# op-synth_2018-05-09.net
KiCad netlist of a schematic drawn in EAGLE
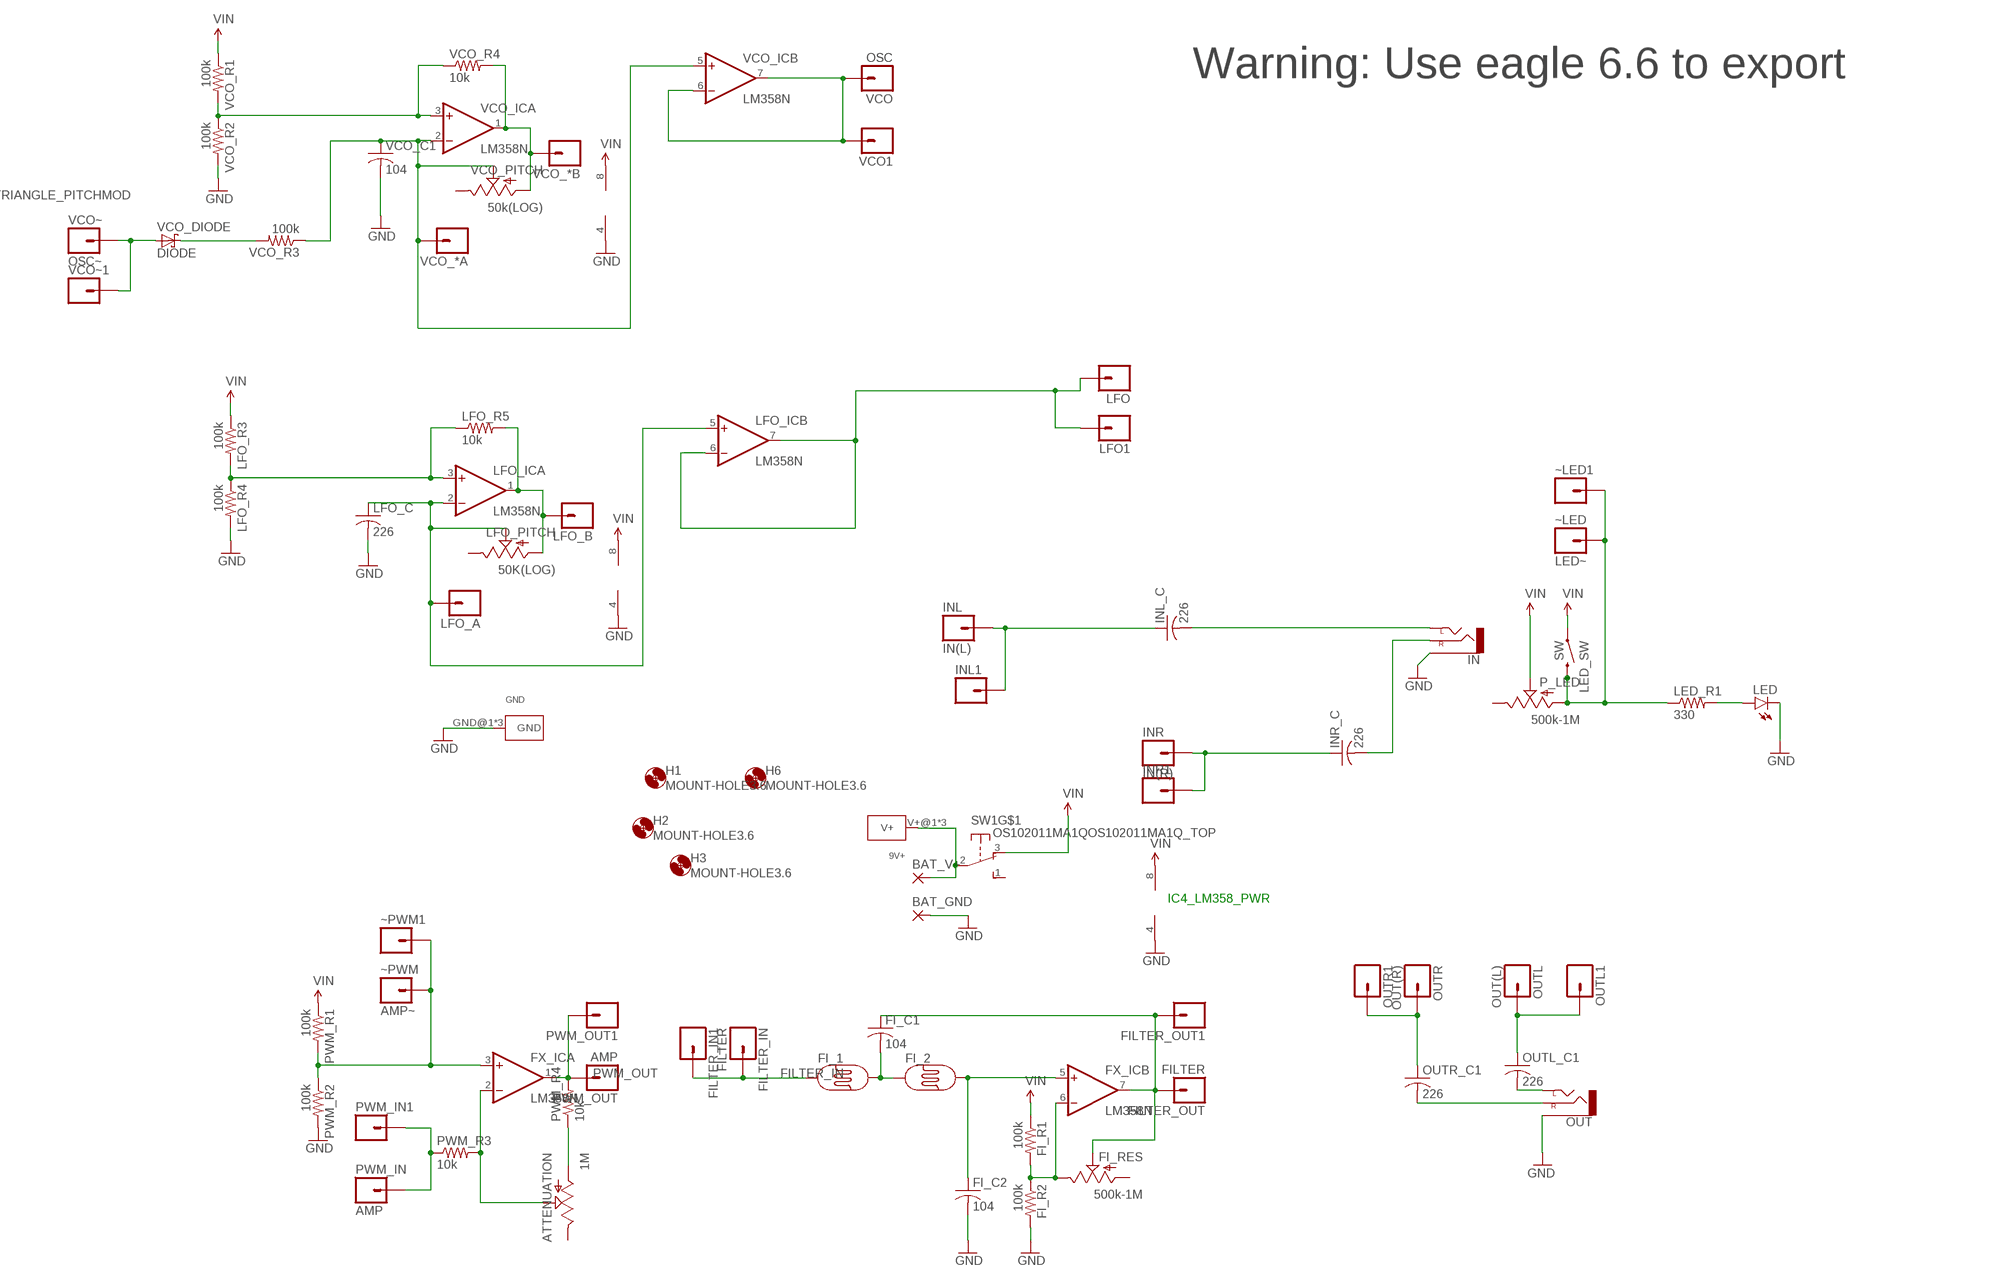
[diagram p0: schematic, sheet 1]

(export (version "E")
  (design (tool "Eeschema 10.0.6"))
  (components
    (comp (ref "9V+")
      (value "KEYSTONE-629+")
      (footprint "eagle-import:KEYSTONE_BATTAERY_TERMINAL-629+")
      (libsource (lib "eagle-import") (part "KEYSTONE-629+"))
    )
    (comp (ref "ATTENUATION")
      (value "1M")
      (footprint "eagle-import:TRIM_POT")
      (libsource (lib "eagle-import") (part "POTTRIM"))
    )
    (comp (ref "BAT_GND")
      (value "3,81/1,4")
      (footprint "eagle-import:3,81_1,4")
      (libsource (lib "eagle-import") (part "3,81/1,4"))
    )
    (comp (ref "BAT_V+")
      (value "3,81/1,4")
      (footprint "eagle-import:3,81_1,4")
      (libsource (lib "eagle-import") (part "3,81/1,4"))
    )
    (comp (ref "FILTER_IN")
      (value "FILTER")
      (footprint "eagle-import:1X01_SIDE_NAME")
      (libsource (lib "eagle-import") (part "HEADER-1X1"))
    )
    (comp (ref "FILTER_IN1")
      (value "HEADER-1X1")
      (footprint "eagle-import:1X01_SIDE_NAME")
      (libsource (lib "eagle-import") (part "HEADER-1X1"))
    )
    (comp (ref "FILTER_OUT")
      (value "FILTER")
      (footprint "eagle-import:1X01_SIDE_NAME")
      (libsource (lib "eagle-import") (part "HEADER-1X1"))
    )
    (comp (ref "FILTER_OUT1")
      (value "HEADER-1X1")
      (footprint "eagle-import:1X01_SIDE_NAME")
      (libsource (lib "eagle-import") (part "HEADER-1X1"))
    )
    (comp (ref "FI_1")
      (value "PHOTOCELLPTH")
      (footprint "eagle-import:PHOTOCELL")
      (libsource (lib "eagle-import") (part "PHOTOCELLPTH"))
    )
    (comp (ref "FI_2")
      (value "PHOTOCELLPTH")
      (footprint "eagle-import:PHOTOCELL")
      (libsource (lib "eagle-import") (part "PHOTOCELLPTH"))
    )
    (comp (ref "FI_C1")
      (value "104")
      (footprint "eagle-import:C050-024X044")
      (libsource (lib "eagle-import") (part "resistor_C-US050-024X044"))
    )
    (comp (ref "FI_C2")
      (value "104")
      (footprint "eagle-import:C050-024X044")
      (libsource (lib "eagle-import") (part "resistor_C-US050-024X044"))
    )
    (comp (ref "FI_R1")
      (value "100k")
      (footprint "eagle-import:0204_7")
      (libsource (lib "eagle-import") (part "R-US_0204/7"))
    )
    (comp (ref "FI_R2")
      (value "100k")
      (footprint "eagle-import:0204_7")
      (libsource (lib "eagle-import") (part "R-US_0204/7"))
    )
    (comp (ref "FI_RES")
      (value "500k-1M")
      (footprint "eagle-import:ALPS_POT")
      (libsource (lib "eagle-import") (part "POT"))
    )
    (comp (ref "FX_IC")
      (value "LM358N")
      (footprint "eagle-import:DIL08")
      (libsource (lib "eagle-import") (part "LM358N"))
    )
    (comp (ref "GND")
      (value "KEYSTONE-629")
      (footprint "eagle-import:KEYSTONE_AA_AAA_BATTERY_TERMINAL-629")
      (libsource (lib "eagle-import") (part "KEYSTONE-629"))
    )
    (comp (ref "H1")
      (value "MOUNT-HOLE3.6")
      (footprint "eagle-import:3,6")
      (libsource (lib "eagle-import") (part "MOUNT-HOLE3.6"))
    )
    (comp (ref "H2")
      (value "MOUNT-HOLE3.6")
      (footprint "eagle-import:3,6")
      (libsource (lib "eagle-import") (part "MOUNT-HOLE3.6"))
    )
    (comp (ref "H3")
      (value "MOUNT-HOLE3.6")
      (footprint "eagle-import:3,6")
      (libsource (lib "eagle-import") (part "MOUNT-HOLE3.6"))
    )
    (comp (ref "H6")
      (value "MOUNT-HOLE3.6")
      (footprint "eagle-import:3,6")
      (libsource (lib "eagle-import") (part "MOUNT-HOLE3.6"))
    )
    (comp (ref "IN")
      (value "AUDIO-JACKPTH")
      (footprint "eagle-import:AUDIO-JACK")
      (libsource (lib "eagle-import") (part "AUDIO-JACKPTH"))
    )
    (comp (ref "INL")
      (value "IN(L)")
      (footprint "eagle-import:1X01_SIDE_NAME")
      (libsource (lib "eagle-import") (part "HEADER-1X1"))
    )
    (comp (ref "INL1")
      (value "HEADER-1X1")
      (footprint "eagle-import:1X01_SIDE_NAME")
      (libsource (lib "eagle-import") (part "HEADER-1X1"))
    )
    (comp (ref "INL_C")
      (value "226")
      (footprint "eagle-import:C050-024X044")
      (libsource (lib "eagle-import") (part "C-US050-024X044"))
    )
    (comp (ref "INR")
      (value "IN(R)")
      (footprint "eagle-import:1X01_SIDE_NAME")
      (libsource (lib "eagle-import") (part "HEADER-1X1"))
    )
    (comp (ref "INR1")
      (value "HEADER-1X1")
      (footprint "eagle-import:1X01_SIDE_NAME")
      (libsource (lib "eagle-import") (part "HEADER-1X1"))
    )
    (comp (ref "INR_C")
      (value "226")
      (footprint "eagle-import:C050-024X044")
      (libsource (lib "eagle-import") (part "C-US050-024X044"))
    )
    (comp (ref "LED")
      (value "LED5MM")
      (footprint "eagle-import:LED5MM")
      (libsource (lib "eagle-import") (part "LED5MM"))
    )
    (comp (ref "LED_R1")
      (value "330")
      (footprint "eagle-import:0204_7")
      (libsource (lib "eagle-import") (part "R-US_0204/7"))
    )
    (comp (ref "LED_SW")
      (value "SW")
      (footprint "eagle-import:TACTILE-PTH-12MM")
      (libsource (lib "eagle-import") (part "SWITCH-MOMENTARY-212MM"))
    )
    (comp (ref "LFO")
      (value "HEADER-1X1")
      (footprint "eagle-import:1X01_SIDE_NAME")
      (libsource (lib "eagle-import") (part "HEADER-1X1"))
    )
    (comp (ref "LFO1")
      (value "HEADER-1X1")
      (footprint "eagle-import:1X01_SIDE_NAME")
      (libsource (lib "eagle-import") (part "HEADER-1X1"))
    )
    (comp (ref "LFO_A")
      (value "HEADER-1X1")
      (footprint "eagle-import:1X01_SIDE_NAME")
      (libsource (lib "eagle-import") (part "HEADER-1X1"))
    )
    (comp (ref "LFO_B")
      (value "HEADER-1X1")
      (footprint "eagle-import:1X01_SIDE_NAME")
      (libsource (lib "eagle-import") (part "HEADER-1X1"))
    )
    (comp (ref "LFO_C")
      (value "226")
      (footprint "eagle-import:C050-024X044")
      (libsource (lib "eagle-import") (part "resistor_C-US050-024X044"))
    )
    (comp (ref "LFO_IC")
      (value "LM358N")
      (footprint "eagle-import:DIL08")
      (libsource (lib "eagle-import") (part "LM358N"))
    )
    (comp (ref "LFO_PITCH")
      (value "50K(LOG)")
      (footprint "eagle-import:ALPS_POT")
      (libsource (lib "eagle-import") (part "POT"))
    )
    (comp (ref "LFO_R3")
      (value "100k")
      (footprint "eagle-import:0204_7")
      (libsource (lib "eagle-import") (part "R-US_0204/7"))
    )
    (comp (ref "LFO_R4")
      (value "100k")
      (footprint "eagle-import:0204_7")
      (libsource (lib "eagle-import") (part "R-US_0204/7"))
    )
    (comp (ref "LFO_R5")
      (value "10k")
      (footprint "eagle-import:0204_7")
      (libsource (lib "eagle-import") (part "R-US_0204/7"))
    )
    (comp (ref "OUT")
      (value "AUDIO-JACKPTH")
      (footprint "eagle-import:AUDIO-JACK")
      (libsource (lib "eagle-import") (part "AUDIO-JACKPTH"))
    )
    (comp (ref "OUTL")
      (value "OUT(L)")
      (footprint "eagle-import:1X01_SIDE_NAME")
      (libsource (lib "eagle-import") (part "HEADER-1X1"))
    )
    (comp (ref "OUTL1")
      (value "HEADER-1X1")
      (footprint "eagle-import:1X01_SIDE_NAME")
      (libsource (lib "eagle-import") (part "HEADER-1X1"))
    )
    (comp (ref "OUTL_C1")
      (value "226")
      (footprint "eagle-import:C050-024X044")
      (libsource (lib "eagle-import") (part "C-US050-024X044"))
    )
    (comp (ref "OUTR")
      (value "OUT(R)")
      (footprint "eagle-import:1X01_SIDE_NAME")
      (libsource (lib "eagle-import") (part "HEADER-1X1"))
    )
    (comp (ref "OUTR1")
      (value "HEADER-1X1")
      (footprint "eagle-import:1X01_SIDE_NAME")
      (libsource (lib "eagle-import") (part "HEADER-1X1"))
    )
    (comp (ref "OUTR_C1")
      (value "226")
      (footprint "eagle-import:C050-024X044")
      (libsource (lib "eagle-import") (part "C-US050-024X044"))
    )
    (comp (ref "PWM_IN")
      (value "AMP")
      (footprint "eagle-import:1X01_SIDE_NAME")
      (libsource (lib "eagle-import") (part "HEADER-1X1"))
    )
    (comp (ref "PWM_IN1")
      (value "HEADER-1X1")
      (footprint "eagle-import:1X01_SIDE_NAME")
      (libsource (lib "eagle-import") (part "HEADER-1X1"))
    )
    (comp (ref "PWM_OUT")
      (value "AMP")
      (footprint "eagle-import:1X01_SIDE_NAME")
      (libsource (lib "eagle-import") (part "HEADER-1X1"))
    )
    (comp (ref "PWM_OUT1")
      (value "HEADER-1X1")
      (footprint "eagle-import:1X01_SIDE_NAME")
      (libsource (lib "eagle-import") (part "HEADER-1X1"))
    )
    (comp (ref "PWM_R1")
      (value "100k")
      (footprint "eagle-import:0204_7")
      (libsource (lib "eagle-import") (part "R-US_0204/7"))
    )
    (comp (ref "PWM_R2")
      (value "100k")
      (footprint "eagle-import:0204_7")
      (libsource (lib "eagle-import") (part "R-US_0204/7"))
    )
    (comp (ref "PWM_R3")
      (value "10k")
      (footprint "eagle-import:0204_7")
      (libsource (lib "eagle-import") (part "R-US_0204/7"))
    )
    (comp (ref "PWM_R4")
      (value "10k")
      (footprint "eagle-import:0204_7")
      (libsource (lib "eagle-import") (part "R-US_0204/7"))
    )
    (comp (ref "P_LED")
      (value "500k-1M")
      (footprint "eagle-import:ALPS_POT")
      (libsource (lib "eagle-import") (part "POT"))
    )
    (comp (ref "SW1")
      (value "OS102011MA1QOS102011MA1Q_TOP")
      (footprint "eagle-import:OS102011MA1Q")
      (libsource (lib "eagle-import") (part "OS102011MA1QOS102011MA1Q_TOP"))
    )
    (comp (ref "VCO")
      (value "OSC")
      (footprint "eagle-import:1X01_SIDE_NAME")
      (libsource (lib "eagle-import") (part "HEADER-1X1"))
    )
    (comp (ref "VCO1")
      (value "HEADER-1X1")
      (footprint "eagle-import:1X01_SIDE_NAME")
      (libsource (lib "eagle-import") (part "HEADER-1X1"))
    )
    (comp (ref "VCO_*A")
      (value "HEADER-1X1")
      (footprint "eagle-import:1X01_SIDE_NAME")
      (libsource (lib "eagle-import") (part "HEADER-1X1"))
    )
    (comp (ref "VCO_*B")
      (value "HEADER-1X1")
      (footprint "eagle-import:1X01_SIDE_NAME")
      (libsource (lib "eagle-import") (part "HEADER-1X1"))
    )
    (comp (ref "VCO_C1")
      (value "104")
      (footprint "eagle-import:C050-024X044")
      (libsource (lib "eagle-import") (part "C-US050-024X044"))
    )
    (comp (ref "VCO_DIODE")
      (value "DIODE")
      (footprint "eagle-import:DO41-7")
      (libsource (lib "eagle-import") (part "SCHOTTKY-DIODEDO41-7"))
    )
    (comp (ref "VCO_IC")
      (value "LM358N")
      (footprint "eagle-import:DIL08")
      (libsource (lib "eagle-import") (part "LM358N"))
    )
    (comp (ref "VCO_PITCH")
      (value "50k(LOG)")
      (footprint "eagle-import:ALPS_POT")
      (libsource (lib "eagle-import") (part "POT"))
    )
    (comp (ref "VCO_R1")
      (value "100k")
      (footprint "eagle-import:0204_7")
      (libsource (lib "eagle-import") (part "R-US_0204/7"))
    )
    (comp (ref "VCO_R2")
      (value "100k")
      (footprint "eagle-import:0204_7")
      (libsource (lib "eagle-import") (part "R-US_0204/7"))
    )
    (comp (ref "VCO_R3")
      (value "100k")
      (footprint "eagle-import:0204_7")
      (libsource (lib "eagle-import") (part "R-US_0204/7"))
    )
    (comp (ref "VCO_R4")
      (value "10k")
      (footprint "eagle-import:0204_7")
      (libsource (lib "eagle-import") (part "R-US_0204/7"))
    )
    (comp (ref "VCO~")
      (value "OSC~")
      (footprint "eagle-import:1X01_SIDE_NAME")
      (libsource (lib "eagle-import") (part "HEADER-1X1"))
    )
    (comp (ref "VCO~1")
      (value "HEADER-1X1")
      (footprint "eagle-import:1X01_SIDE_NAME")
      (libsource (lib "eagle-import") (part "HEADER-1X1"))
    )
    (comp (ref "~LED")
      (value "LED~")
      (footprint "eagle-import:1X01_SIDE_NAME")
      (libsource (lib "eagle-import") (part "HEADER-1X1"))
    )
    (comp (ref "~LED1")
      (value "HEADER-1X1")
      (footprint "eagle-import:1X01_SIDE_NAME")
      (libsource (lib "eagle-import") (part "HEADER-1X1"))
    )
    (comp (ref "~PWM")
      (value "AMP~")
      (footprint "eagle-import:1X01_SIDE_NAME")
      (libsource (lib "eagle-import") (part "HEADER-1X1"))
    )
    (comp (ref "~PWM1")
      (value "HEADER-1X1")
      (footprint "eagle-import:1X01_SIDE_NAME")
      (libsource (lib "eagle-import") (part "HEADER-1X1"))
    )
  )
  (nets
    (net (code "1") (name "/FILTER_IN") (class "Default")
      (node (ref "FILTER_IN") (pin "1") (pinfunction "1_1") (pintype "passive"))
      (node (ref "FILTER_IN1") (pin "1") (pinfunction "1_1") (pintype "passive"))
      (node (ref "FI_1") (pin "1") (pinfunction "P$1_1") (pintype "bidirectional"))
    )
    (net (code "2") (name "/PWM_OUT") (class "Default")
      (node (ref "FX_IC") (pin "1") (pinfunction "OUT_1") (pintype "output"))
      (node (ref "PWM_OUT") (pin "1") (pinfunction "1_1") (pintype "passive"))
      (node (ref "PWM_OUT1") (pin "1") (pinfunction "1_1") (pintype "passive"))
      (node (ref "PWM_R4") (pin "2") (pinfunction "2_2") (pintype "passive"))
    )
    (net (code "3") (name "/TRIANGLE_PITCHMOD") (class "Default")
      (node (ref "VCO_DIODE") (pin "A") (pinfunction "A_A") (pintype "passive"))
      (node (ref "VCO~") (pin "1") (pinfunction "1_1") (pintype "passive"))
      (node (ref "VCO~1") (pin "1") (pinfunction "1_1") (pintype "passive"))
    )
    (net (code "4") (name "GND") (class "Default")
      (node (ref "BAT_GND") (pin "1") (pinfunction "P_1") (pintype "passive"))
      (node (ref "FI_C2") (pin "2") (pinfunction "2_2") (pintype "passive"))
      (node (ref "FI_R2") (pin "2") (pinfunction "2_2") (pintype "passive"))
      (node (ref "FX_IC") (pin "4") (pinfunction "V-_4") (pintype "power_in"))
      (node (ref "GND") (pin "GND@1") (pinfunction "GND_GND@1") (pintype "power_in"))
      (node (ref "GND") (pin "GND@2") (pinfunction "GND_GND@2") (pintype "power_in"))
      (node (ref "GND") (pin "GND@3") (pinfunction "GND_GND@3") (pintype "power_in"))
      (node (ref "IN") (pin "SLEEVE") (pinfunction "SLEEVE_SLEEVE") (pintype "bidirectional"))
      (node (ref "LED") (pin "K") (pinfunction "C_K") (pintype "passive"))
      (node (ref "LFO_C") (pin "2") (pinfunction "2_2") (pintype "passive"))
      (node (ref "LFO_IC") (pin "4") (pinfunction "V-_4") (pintype "power_in"))
      (node (ref "LFO_R4") (pin "2") (pinfunction "2_2") (pintype "passive"))
      (node (ref "OUT") (pin "SLEEVE") (pinfunction "SLEEVE_SLEEVE") (pintype "bidirectional"))
      (node (ref "PWM_R2") (pin "2") (pinfunction "2_2") (pintype "passive"))
      (node (ref "VCO_C1") (pin "2") (pinfunction "2_2") (pintype "passive"))
      (node (ref "VCO_IC") (pin "4") (pinfunction "V-_4") (pintype "power_in"))
      (node (ref "VCO_R2") (pin "2") (pinfunction "2_2") (pintype "passive"))
    )
    (net (code "5") (name "Net-(ATTENUATION-A)") (class "Default")
      (node (ref "ATTENUATION") (pin "3") (pinfunction "A_3") (pintype "passive"))
      (node (ref "PWM_R4") (pin "1") (pinfunction "1_1") (pintype "passive"))
    )
    (net (code "6") (name "Net-(ATTENUATION-S)") (class "Default")
      (node (ref "ATTENUATION") (pin "1") (pinfunction "S_1") (pintype "passive"))
      (node (ref "FX_IC") (pin "2") (pinfunction "-IN_2") (pintype "input"))
      (node (ref "PWM_R3") (pin "2") (pinfunction "2_2") (pintype "passive"))
    )
    (net (code "7") (name "Net-(BAT_V+-P)") (class "Default")
      (node (ref "9V+") (pin "V+@1") (pinfunction "V+_V+@1") (pintype "power_in"))
      (node (ref "9V+") (pin "V+@2") (pinfunction "V+_V+@2") (pintype "power_in"))
      (node (ref "9V+") (pin "V+@3") (pinfunction "V+_V+@3") (pintype "power_in"))
      (node (ref "BAT_V+") (pin "1") (pinfunction "P_1") (pintype "passive"))
      (node (ref "SW1") (pin "2") (pinfunction "P_2") (pintype "passive"))
    )
    (net (code "8") (name "Net-(FI_1-P$2)") (class "Default")
      (node (ref "FI_1") (pin "2") (pinfunction "P$2_2") (pintype "bidirectional"))
      (node (ref "FI_2") (pin "1") (pinfunction "P$1_1") (pintype "bidirectional"))
      (node (ref "FI_C1") (pin "2") (pinfunction "2_2") (pintype "passive"))
    )
    (net (code "9") (name "Net-(FI_2-P$2)") (class "Default")
      (node (ref "FI_2") (pin "2") (pinfunction "P$2_2") (pintype "bidirectional"))
      (node (ref "FI_C2") (pin "1") (pinfunction "1_1") (pintype "passive"))
      (node (ref "FX_IC") (pin "5") (pinfunction "+IN_5") (pintype "input"))
    )
    (net (code "10") (name "Net-(FI_RES-E)") (class "Default")
      (node (ref "FI_R1") (pin "2") (pinfunction "2_2") (pintype "passive"))
      (node (ref "FI_R2") (pin "1") (pinfunction "1_1") (pintype "passive"))
      (node (ref "FI_RES") (pin "P$1") (pinfunction "E_P$1") (pintype "passive"))
      (node (ref "FX_IC") (pin "6") (pinfunction "-IN_6") (pintype "input"))
    )
    (net (code "11") (name "Net-(FI_RES-S)") (class "Default")
      (node (ref "FILTER_OUT") (pin "1") (pinfunction "1_1") (pintype "passive"))
      (node (ref "FILTER_OUT1") (pin "1") (pinfunction "1_1") (pintype "passive"))
      (node (ref "FI_C1") (pin "1") (pinfunction "1_1") (pintype "passive"))
      (node (ref "FI_RES") (pin "P$2") (pinfunction "S_P$2") (pintype "passive"))
      (node (ref "FX_IC") (pin "7") (pinfunction "OUT_7") (pintype "output"))
    )
    (net (code "12") (name "Net-(FX_ICA-+IN)") (class "Default")
      (node (ref "FX_IC") (pin "3") (pinfunction "+IN_3") (pintype "input"))
      (node (ref "PWM_R1") (pin "2") (pinfunction "2_2") (pintype "passive"))
      (node (ref "PWM_R2") (pin "1") (pinfunction "1_1") (pintype "passive"))
      (node (ref "~PWM") (pin "1") (pinfunction "1_1") (pintype "passive"))
      (node (ref "~PWM1") (pin "1") (pinfunction "1_1") (pintype "passive"))
    )
    (net (code "13") (name "Net-(IN-LEFT)") (class "Default")
      (node (ref "IN") (pin "TIP") (pinfunction "LEFT_TIP") (pintype "bidirectional"))
      (node (ref "INL_C") (pin "2") (pinfunction "2_2") (pintype "passive"))
    )
    (net (code "14") (name "Net-(IN-RIGHT)") (class "Default")
      (node (ref "IN") (pin "RING") (pinfunction "RIGHT_RING") (pintype "bidirectional"))
      (node (ref "INR_C") (pin "2") (pinfunction "2_2") (pintype "passive"))
    )
    (net (code "15") (name "Net-(INL-Pad1)") (class "Default")
      (node (ref "INL") (pin "1") (pinfunction "1_1") (pintype "passive"))
      (node (ref "INL1") (pin "1") (pinfunction "1_1") (pintype "passive"))
      (node (ref "INL_C") (pin "1") (pinfunction "1_1") (pintype "passive"))
    )
    (net (code "16") (name "Net-(INR-Pad1)") (class "Default")
      (node (ref "INR") (pin "1") (pinfunction "1_1") (pintype "passive"))
      (node (ref "INR1") (pin "1") (pinfunction "1_1") (pintype "passive"))
      (node (ref "INR_C") (pin "1") (pinfunction "1_1") (pintype "passive"))
    )
    (net (code "17") (name "Net-(LED-PadA)") (class "Default")
      (node (ref "LED") (pin "A") (pinfunction "A_A") (pintype "passive"))
      (node (ref "LED_R1") (pin "2") (pinfunction "2_2") (pintype "passive"))
    )
    (net (code "18") (name "Net-(LED_SW-2)") (class "Default")
      (node (ref "LED_R1") (pin "1") (pinfunction "1_1") (pintype "passive"))
      (node (ref "LED_SW") (pin "3") (pinfunction "2_3") (pintype "passive"))
      (node (ref "P_LED") (pin "P$3") (pinfunction "A_P$3") (pintype "passive"))
      (node (ref "~LED") (pin "1") (pinfunction "1_1") (pintype "passive"))
      (node (ref "~LED1") (pin "1") (pinfunction "1_1") (pintype "passive"))
    )
    (net (code "19") (name "Net-(LFO_ICA-+IN)") (class "Default")
      (node (ref "LFO_IC") (pin "3") (pinfunction "+IN_3") (pintype "input"))
      (node (ref "LFO_R3") (pin "2") (pinfunction "2_2") (pintype "passive"))
      (node (ref "LFO_R4") (pin "1") (pinfunction "1_1") (pintype "passive"))
      (node (ref "LFO_R5") (pin "1") (pinfunction "1_1") (pintype "passive"))
    )
    (net (code "20") (name "Net-(LFO_ICA--IN)") (class "Default")
      (node (ref "LFO_A") (pin "1") (pinfunction "1_1") (pintype "passive"))
      (node (ref "LFO_C") (pin "1") (pinfunction "1_1") (pintype "passive"))
      (node (ref "LFO_IC") (pin "2") (pinfunction "-IN_2") (pintype "input"))
      (node (ref "LFO_IC") (pin "5") (pinfunction "+IN_5") (pintype "input"))
      (node (ref "LFO_PITCH") (pin "P$2") (pinfunction "S_P$2") (pintype "passive"))
    )
    (net (code "21") (name "Net-(LFO_ICA-OUT)") (class "Default")
      (node (ref "LFO_B") (pin "1") (pinfunction "1_1") (pintype "passive"))
      (node (ref "LFO_IC") (pin "1") (pinfunction "OUT_1") (pintype "output"))
      (node (ref "LFO_PITCH") (pin "P$3") (pinfunction "A_P$3") (pintype "passive"))
      (node (ref "LFO_R5") (pin "2") (pinfunction "2_2") (pintype "passive"))
    )
    (net (code "22") (name "Net-(LFO_ICB--IN)") (class "Default")
      (node (ref "LFO") (pin "1") (pinfunction "1_1") (pintype "passive"))
      (node (ref "LFO1") (pin "1") (pinfunction "1_1") (pintype "passive"))
      (node (ref "LFO_IC") (pin "6") (pinfunction "-IN_6") (pintype "input"))
      (node (ref "LFO_IC") (pin "7") (pinfunction "OUT_7") (pintype "output"))
    )
    (net (code "23") (name "Net-(OUT-LEFT)") (class "Default")
      (node (ref "OUT") (pin "TIP") (pinfunction "LEFT_TIP") (pintype "bidirectional"))
      (node (ref "OUTL_C1") (pin "2") (pinfunction "2_2") (pintype "passive"))
    )
    (net (code "24") (name "Net-(OUT-RIGHT)") (class "Default")
      (node (ref "OUT") (pin "RING") (pinfunction "RIGHT_RING") (pintype "bidirectional"))
      (node (ref "OUTR_C1") (pin "2") (pinfunction "2_2") (pintype "passive"))
    )
    (net (code "25") (name "Net-(OUTL-Pad1)") (class "Default")
      (node (ref "OUTL") (pin "1") (pinfunction "1_1") (pintype "passive"))
      (node (ref "OUTL1") (pin "1") (pinfunction "1_1") (pintype "passive"))
      (node (ref "OUTL_C1") (pin "1") (pinfunction "1_1") (pintype "passive"))
    )
    (net (code "26") (name "Net-(OUTR-Pad1)") (class "Default")
      (node (ref "OUTR") (pin "1") (pinfunction "1_1") (pintype "passive"))
      (node (ref "OUTR1") (pin "1") (pinfunction "1_1") (pintype "passive"))
      (node (ref "OUTR_C1") (pin "1") (pinfunction "1_1") (pintype "passive"))
    )
    (net (code "27") (name "Net-(PWM_IN-Pad1)") (class "Default")
      (node (ref "PWM_IN") (pin "1") (pinfunction "1_1") (pintype "passive"))
      (node (ref "PWM_IN1") (pin "1") (pinfunction "1_1") (pintype "passive"))
      (node (ref "PWM_R3") (pin "1") (pinfunction "1_1") (pintype "passive"))
    )
    (net (code "28") (name "Net-(VCO_DIODE-PadC)") (class "Default")
      (node (ref "VCO_DIODE") (pin "C") (pinfunction "C_C") (pintype "passive"))
      (node (ref "VCO_R3") (pin "2") (pinfunction "2_2") (pintype "passive"))
    )
    (net (code "29") (name "Net-(VCO_ICA-+IN)") (class "Default")
      (node (ref "VCO_IC") (pin "3") (pinfunction "+IN_3") (pintype "input"))
      (node (ref "VCO_R1") (pin "2") (pinfunction "2_2") (pintype "passive"))
      (node (ref "VCO_R2") (pin "1") (pinfunction "1_1") (pintype "passive"))
      (node (ref "VCO_R4") (pin "1") (pinfunction "1_1") (pintype "passive"))
    )
    (net (code "30") (name "Net-(VCO_ICA--IN)") (class "Default")
      (node (ref "VCO_*A") (pin "1") (pinfunction "1_1") (pintype "passive"))
      (node (ref "VCO_C1") (pin "1") (pinfunction "1_1") (pintype "passive"))
      (node (ref "VCO_IC") (pin "2") (pinfunction "-IN_2") (pintype "input"))
      (node (ref "VCO_IC") (pin "5") (pinfunction "+IN_5") (pintype "input"))
      (node (ref "VCO_PITCH") (pin "P$2") (pinfunction "S_P$2") (pintype "passive"))
      (node (ref "VCO_R3") (pin "1") (pinfunction "1_1") (pintype "passive"))
    )
    (net (code "31") (name "Net-(VCO_ICA-OUT)") (class "Default")
      (node (ref "VCO_*B") (pin "1") (pinfunction "1_1") (pintype "passive"))
      (node (ref "VCO_IC") (pin "1") (pinfunction "OUT_1") (pintype "output"))
      (node (ref "VCO_PITCH") (pin "P$3") (pinfunction "A_P$3") (pintype "passive"))
      (node (ref "VCO_R4") (pin "2") (pinfunction "2_2") (pintype "passive"))
    )
    (net (code "32") (name "Net-(VCO_ICB--IN)") (class "Default")
      (node (ref "VCO") (pin "1") (pinfunction "1_1") (pintype "passive"))
      (node (ref "VCO1") (pin "1") (pinfunction "1_1") (pintype "passive"))
      (node (ref "VCO_IC") (pin "6") (pinfunction "-IN_6") (pintype "input"))
      (node (ref "VCO_IC") (pin "7") (pinfunction "OUT_7") (pintype "output"))
    )
    (net (code "33") (name "VIN") (class "Default")
      (node (ref "FI_R1") (pin "1") (pinfunction "1_1") (pintype "passive"))
      (node (ref "FX_IC") (pin "8") (pinfunction "V+_8") (pintype "power_in"))
      (node (ref "LED_SW") (pin "1") (pinfunction "1_1") (pintype "passive"))
      (node (ref "LFO_IC") (pin "8") (pinfunction "V+_8") (pintype "power_in"))
      (node (ref "LFO_R3") (pin "1") (pinfunction "1_1") (pintype "passive"))
      (node (ref "PWM_R1") (pin "1") (pinfunction "1_1") (pintype "passive"))
      (node (ref "P_LED") (pin "P$2") (pinfunction "S_P$2") (pintype "passive"))
      (node (ref "SW1") (pin "3") (pinfunction "O_3") (pintype "passive"))
      (node (ref "VCO_IC") (pin "8") (pinfunction "V+_8") (pintype "power_in"))
      (node (ref "VCO_R1") (pin "1") (pinfunction "1_1") (pintype "passive"))
    )
    (net (code "34") (name "unconnected-(ATTENUATION-E-Pad2)") (class "Default")
      (node (ref "ATTENUATION") (pin "2") (pinfunction "E_2") (pintype "passive"))
    )
    (net (code "35") (name "unconnected-(FI_RES-A-PadP$3)") (class "Default")
      (node (ref "FI_RES") (pin "P$3") (pinfunction "A_P$3") (pintype "passive"))
    )
    (net (code "36") (name "unconnected-(LFO_PITCH-E-PadP$1)") (class "Default")
      (node (ref "LFO_PITCH") (pin "P$1") (pinfunction "E_P$1") (pintype "passive"))
    )
    (net (code "37") (name "unconnected-(P_LED-E-PadP$1)") (class "Default")
      (node (ref "P_LED") (pin "P$1") (pinfunction "E_P$1") (pintype "passive"))
    )
    (net (code "38") (name "unconnected-(SW1A-S-Pad1)") (class "Default")
      (node (ref "SW1") (pin "1") (pinfunction "S_1") (pintype "passive"))
    )
    (net (code "39") (name "unconnected-(VCO_PITCH-E-PadP$1)") (class "Default")
      (node (ref "VCO_PITCH") (pin "P$1") (pinfunction "E_P$1") (pintype "passive"))
    )
  )
)
